# isoSPI_UART_Test_Board_rev1.net
KiCad netlist of a schematic drawn in EAGLE
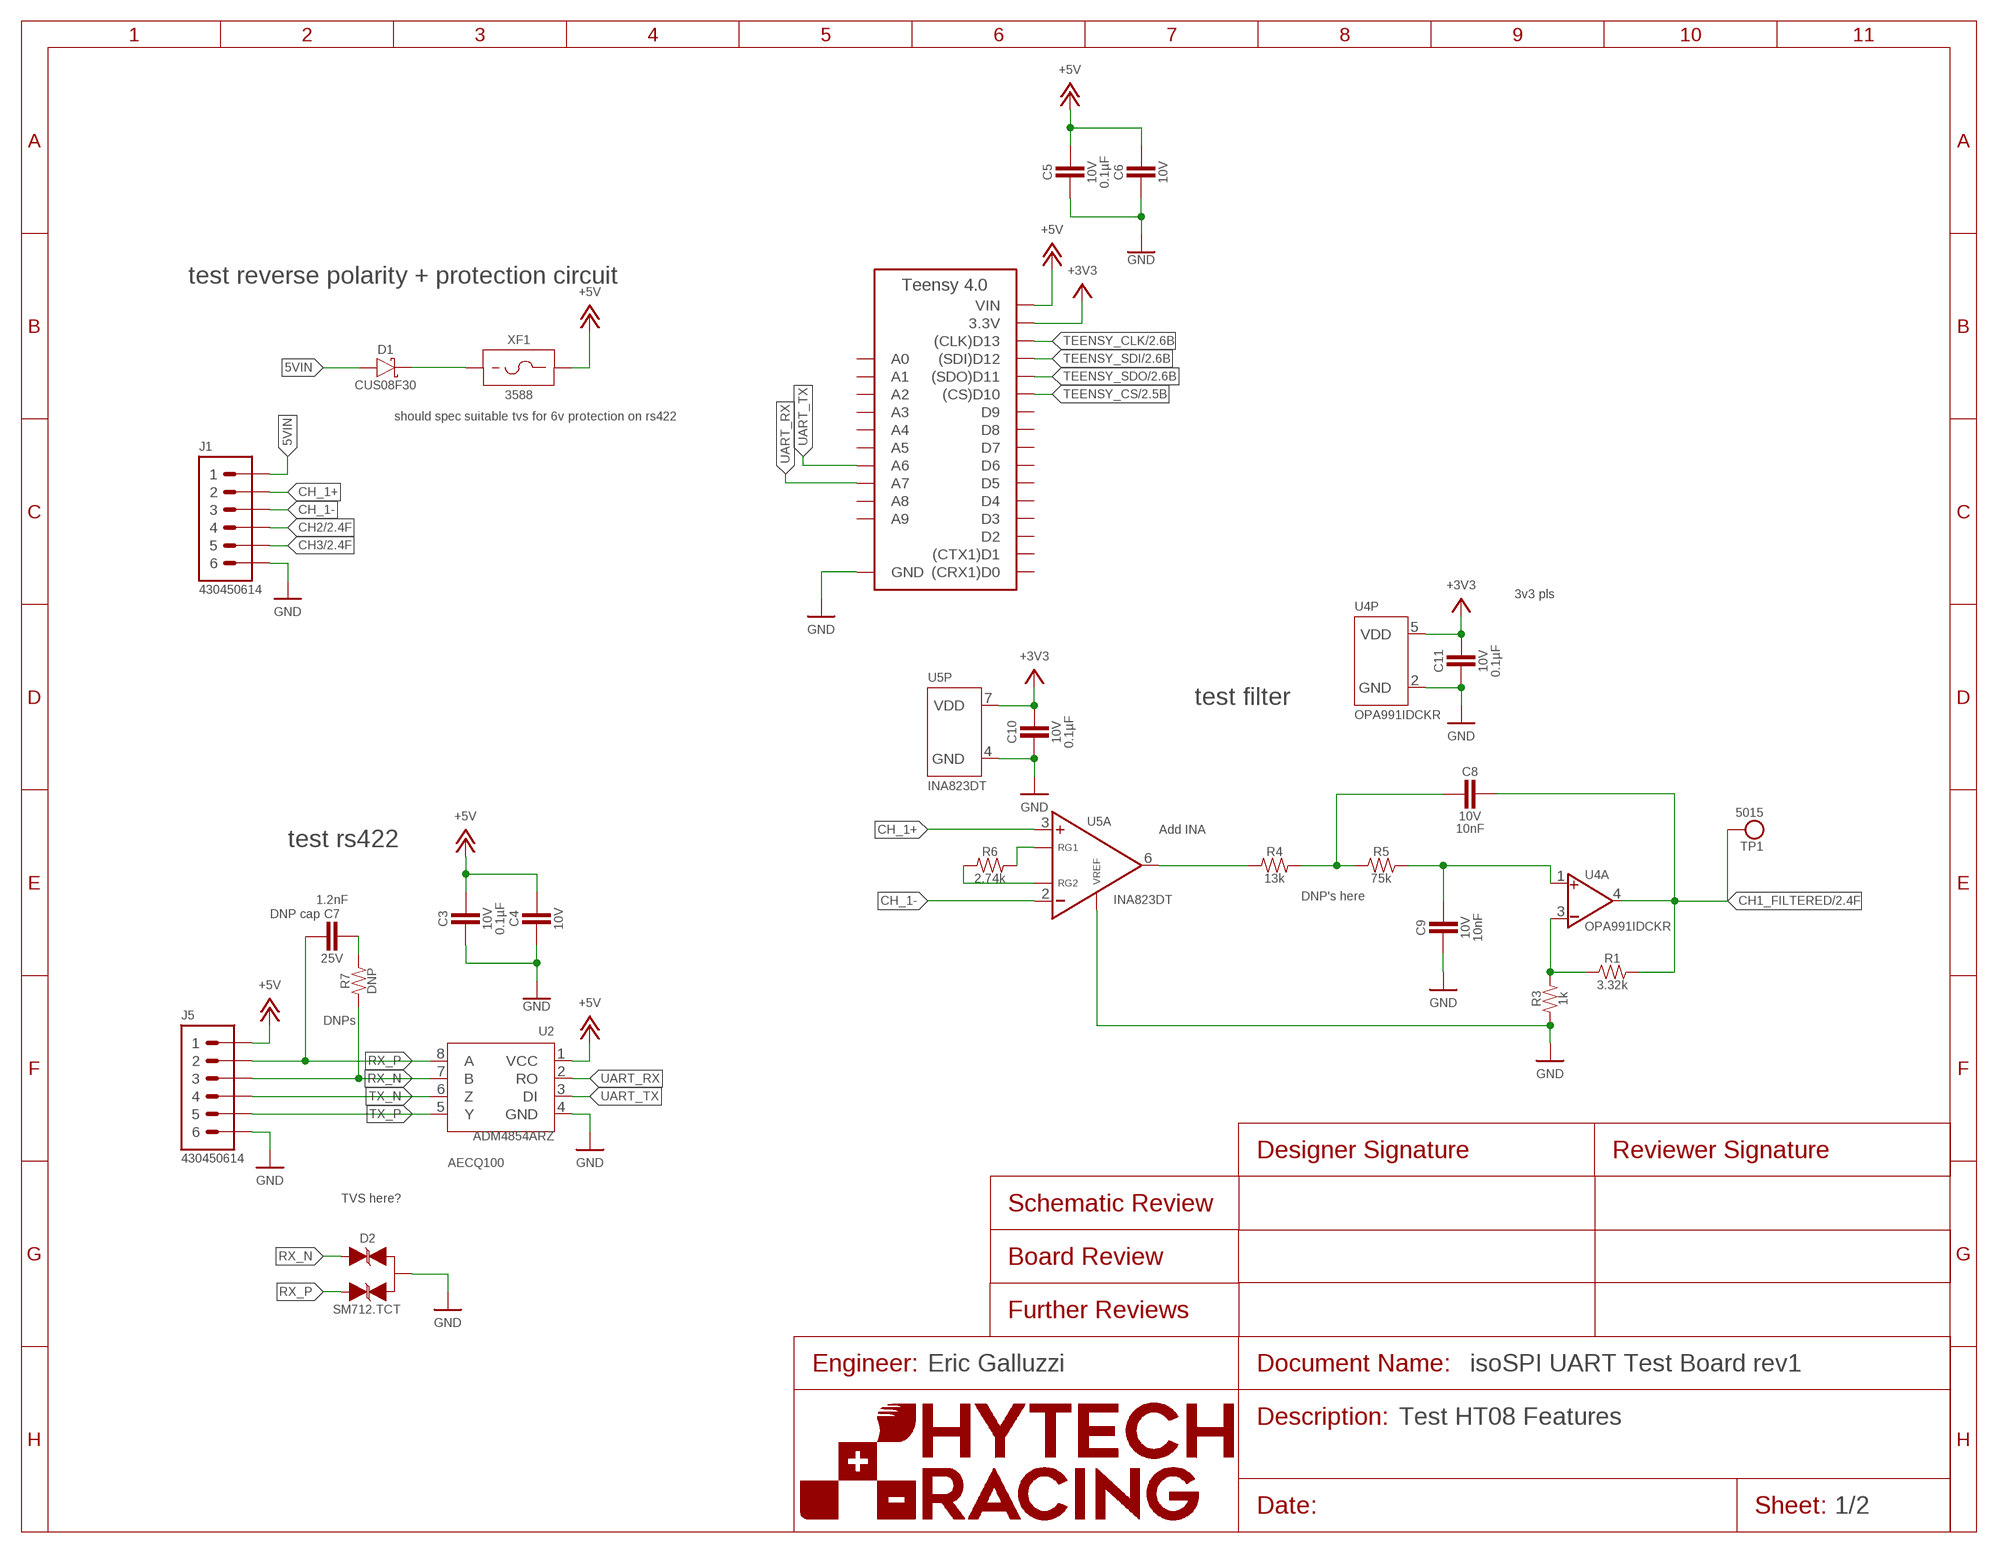
[diagram p0: schematic, sheet 1]
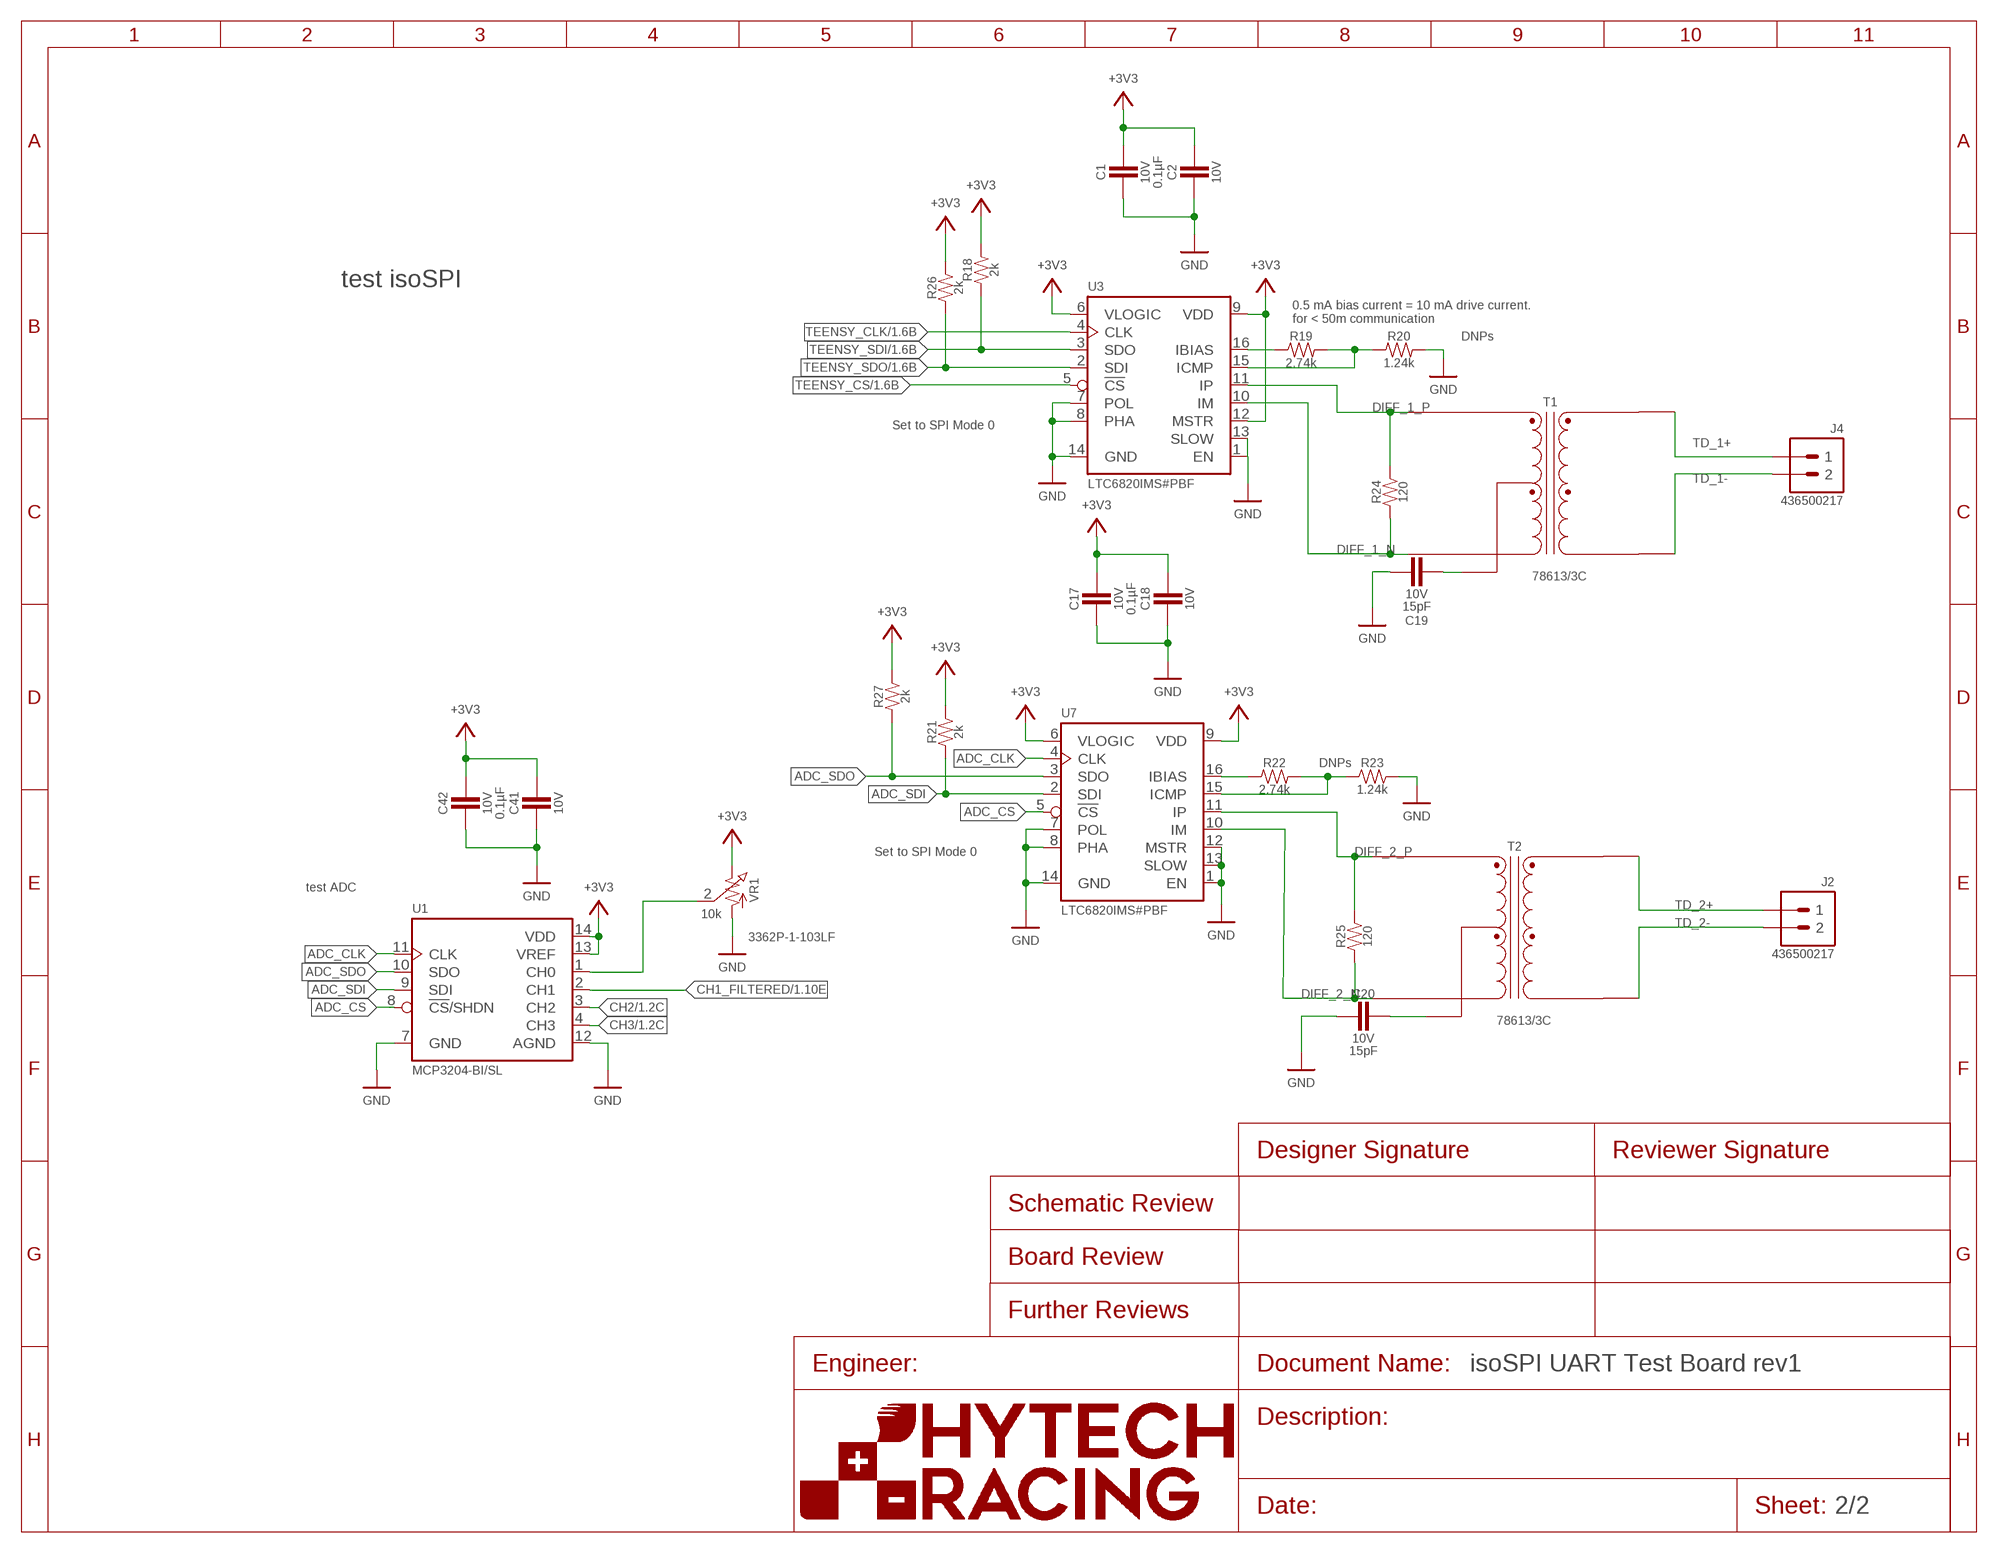
[diagram p1: schematic, sheet 2]

(export (version "E")
  (design (tool "Eeschema 10.0.6"))
  (components
    (comp (ref "C1")
      (value "CAPACITOR_0603_10V_0.1UF")
      (footprint "eagle-import:0603-CAP")
      (fields
        (field (name "CAPACITANCE") "0.1µF")
        (field (name "MANUFACTURER") "Vishay Vitramon")
        (field (name "MPN") "VJ0603Y104JXQPW1BC")
        (field (name "TOLERANCE") "5%")
        (field (name "VOLTAGE") "10V")
      )
      (libsource (lib "eagle-import") (part "CAPACITOR_?_060310V_0.1UF"))
    )
    (comp (ref "C2")
      (value "CAPACITOR_0603_10V_1UF")
      (footprint "eagle-import:0603-CAP")
      (fields
        (field (name "MANUFACTURER") "Yageo")
        (field (name "MPN") "CC0603KRX7R6BB105")
        (field (name "TOLERANCE") "10%")
        (field (name "VOLTAGE") "10V")
      )
      (libsource (lib "eagle-import") (part "CAPACITOR_?_060310V_1UF"))
    )
    (comp (ref "C17")
      (value "CAPACITOR_0603_10V_0.1UF")
      (footprint "eagle-import:0603-CAP")
      (fields
        (field (name "CAPACITANCE") "0.1µF")
        (field (name "MANUFACTURER") "Vishay Vitramon")
        (field (name "MPN") "VJ0603Y104JXQPW1BC")
        (field (name "TOLERANCE") "5%")
        (field (name "VOLTAGE") "10V")
      )
      (libsource (lib "eagle-import") (part "CAPACITOR_?_060310V_0.1UF"))
    )
    (comp (ref "C18")
      (value "CAPACITOR_0603_10V_1UF")
      (footprint "eagle-import:0603-CAP")
      (fields
        (field (name "MANUFACTURER") "Yageo")
        (field (name "MPN") "CC0603KRX7R6BB105")
        (field (name "TOLERANCE") "10%")
        (field (name "VOLTAGE") "10V")
      )
      (libsource (lib "eagle-import") (part "CAPACITOR_?_060310V_1UF"))
    )
    (comp (ref "C19")
      (value "CAPACITOR_0603_10V_15PF")
      (footprint "eagle-import:0603-CAP")
      (fields
        (field (name "CAPACITANCE") "15pF")
        (field (name "MANUFACTURER") "Vishay Vitramon")
        (field (name "MPN") "VJ0603A150FXQPW1BC")
        (field (name "TOLERANCE") "1%")
        (field (name "VOLTAGE") "10V")
      )
      (libsource (lib "eagle-import") (part "CAPACITOR_?_060310V_15PF"))
    )
    (comp (ref "C20")
      (value "CAPACITOR_0603_10V_15PF")
      (footprint "eagle-import:0603-CAP")
      (fields
        (field (name "CAPACITANCE") "15pF")
        (field (name "MANUFACTURER") "Vishay Vitramon")
        (field (name "MPN") "VJ0603A150FXQPW1BC")
        (field (name "TOLERANCE") "1%")
        (field (name "VOLTAGE") "10V")
      )
      (libsource (lib "eagle-import") (part "CAPACITOR_?_060310V_15PF"))
    )
    (comp (ref "C41")
      (value "CAPACITOR_0603_10V_1UF")
      (footprint "eagle-import:0603-CAP")
      (fields
        (field (name "MANUFACTURER") "Yageo")
        (field (name "MPN") "CC0603KRX7R6BB105")
        (field (name "TOLERANCE") "10%")
        (field (name "VOLTAGE") "10V")
      )
      (libsource (lib "eagle-import") (part "CAPACITOR_?_060310V_1UF"))
    )
    (comp (ref "C42")
      (value "CAPACITOR_0603_10V_0.1UF")
      (footprint "eagle-import:0603-CAP")
      (fields
        (field (name "CAPACITANCE") "0.1µF")
        (field (name "MANUFACTURER") "Vishay Vitramon")
        (field (name "MPN") "VJ0603Y104JXQPW1BC")
        (field (name "TOLERANCE") "5%")
        (field (name "VOLTAGE") "10V")
      )
      (libsource (lib "eagle-import") (part "CAPACITOR_?_060310V_0.1UF"))
    )
    (comp (ref "J2")
      (value "CONNECTOR-2_MF_T_V_")
      (footprint "eagle-import:MOLEX_MICROFIT_PTH_VERTICAL_02_SINGLE")
      (fields (field (name "MPN") "436500217") (field (name "MANUFACTURER") "MOLEX"))
      (libsource (lib "eagle-import") (part "CONNECTOR-2_?_MF_T_V"))
    )
    (comp (ref "J4")
      (value "CONNECTOR-2_MF_T_V_")
      (footprint "eagle-import:MOLEX_MICROFIT_PTH_VERTICAL_02_SINGLE")
      (fields (field (name "MPN") "436500217") (field (name "MANUFACTURER") "MOLEX"))
      (libsource (lib "eagle-import") (part "CONNECTOR-2_?_MF_T_V"))
    )
    (comp (ref "R18")
      (value "RESISTOR_0603_2K")
      (footprint "eagle-import:0603-RES")
      (fields
        (field (name "MANUFACTURER") "Panasonic Electronic Components")
        (field (name "MPN") "ERJ-UP3F2001V")
        (field (name "POWER") "0.25W")
        (field (name "RESISTANCE") "2k")
      )
      (libsource (lib "eagle-import") (part "RESISTOR_?_06032K"))
    )
    (comp (ref "R19")
      (value "RESISTOR_0603_2.74K")
      (footprint "eagle-import:0603-RES")
      (fields
        (field (name "MANUFACTURER") "Panasonic Electronic Components")
        (field (name "MPN") "ERJ-PB3B2741V")
        (field (name "POWER") "0.2W")
        (field (name "RESISTANCE") "2.74k")
      )
      (libsource (lib "eagle-import") (part "RESISTOR_?_06032.74K"))
    )
    (comp (ref "R20")
      (value "RESISTOR_0603_1.24K")
      (footprint "eagle-import:0603-RES")
      (fields
        (field (name "MANUFACTURER") "Yageo")
        (field (name "MPN") "RC0603FR-071K24L")
        (field (name "POWER") "0.1W")
        (field (name "RESISTANCE") "1.24k")
      )
      (libsource (lib "eagle-import") (part "RESISTOR_?_06031.24K"))
    )
    (comp (ref "R21")
      (value "RESISTOR_0603_2K")
      (footprint "eagle-import:0603-RES")
      (fields
        (field (name "MANUFACTURER") "Panasonic Electronic Components")
        (field (name "MPN") "ERJ-UP3F2001V")
        (field (name "POWER") "0.25W")
        (field (name "RESISTANCE") "2k")
      )
      (libsource (lib "eagle-import") (part "RESISTOR_?_06032K"))
    )
    (comp (ref "R22")
      (value "RESISTOR_0603_2.74K")
      (footprint "eagle-import:0603-RES")
      (fields
        (field (name "MANUFACTURER") "Panasonic Electronic Components")
        (field (name "MPN") "ERJ-PB3B2741V")
        (field (name "POWER") "0.2W")
        (field (name "RESISTANCE") "2.74k")
      )
      (libsource (lib "eagle-import") (part "RESISTOR_?_06032.74K"))
    )
    (comp (ref "R23")
      (value "RESISTOR_0603_1.24K")
      (footprint "eagle-import:0603-RES")
      (fields
        (field (name "MANUFACTURER") "Yageo")
        (field (name "MPN") "RC0603FR-071K24L")
        (field (name "POWER") "0.1W")
        (field (name "RESISTANCE") "1.24k")
      )
      (libsource (lib "eagle-import") (part "RESISTOR_?_06031.24K"))
    )
    (comp (ref "R24")
      (value "RESISTOR_0603_120")
      (footprint "eagle-import:0603-RES")
      (fields
        (field (name "MANUFACTURER") "Panasonic Electronic Components")
        (field (name "MPN") "ERA-3AEB121V")
        (field (name "POWER") "0.1W")
        (field (name "RESISTANCE") "120")
      )
      (libsource (lib "eagle-import") (part "RESISTOR_?_0603120"))
    )
    (comp (ref "R25")
      (value "RESISTOR_0603_120")
      (footprint "eagle-import:0603-RES")
      (fields
        (field (name "MANUFACTURER") "Panasonic Electronic Components")
        (field (name "MPN") "ERA-3AEB121V")
        (field (name "POWER") "0.1W")
        (field (name "RESISTANCE") "120")
      )
      (libsource (lib "eagle-import") (part "RESISTOR_?_0603120"))
    )
    (comp (ref "R26")
      (value "RESISTOR_0603_2K")
      (footprint "eagle-import:0603-RES")
      (fields
        (field (name "MANUFACTURER") "Panasonic Electronic Components")
        (field (name "MPN") "ERJ-UP3F2001V")
        (field (name "POWER") "0.25W")
        (field (name "RESISTANCE") "2k")
      )
      (libsource (lib "eagle-import") (part "RESISTOR_?_06032K"))
    )
    (comp (ref "R27")
      (value "RESISTOR_0603_2K")
      (footprint "eagle-import:0603-RES")
      (fields
        (field (name "MANUFACTURER") "Panasonic Electronic Components")
        (field (name "MPN") "ERJ-UP3F2001V")
        (field (name "POWER") "0.25W")
        (field (name "RESISTANCE") "2k")
      )
      (libsource (lib "eagle-import") (part "RESISTOR_?_06032K"))
    )
    (comp (ref "T1")
      (value "78613/3C")
      (footprint "eagle-import:78613_3C")
      (fields (field (name "MPN") "78613/3C") (field (name "MANUFACTURER") "Murata Power Solutions"))
      (libsource (lib "eagle-import") (part "78613/3C"))
    )
    (comp (ref "T2")
      (value "78613/3C")
      (footprint "eagle-import:78613_3C")
      (fields (field (name "MPN") "78613/3C") (field (name "MANUFACTURER") "Murata Power Solutions"))
      (libsource (lib "eagle-import") (part "78613/3C"))
    )
    (comp (ref "U1")
      (value "MCP3204")
      (footprint "eagle-import:SOIC-14")
      (fields (field (name "MPN") "MCP3204-BI/SL") (field (name "MANUFACTURER") "Microchip Technology"))
      (libsource (lib "eagle-import") (part "MCP3204"))
    )
    (comp (ref "U3")
      (value "LTC6820")
      (footprint "eagle-import:MSOP-16")
      (fields (field (name "MPN") "LTC6820IMS#PBF") (field (name "MANUFACTURER") "Analog Devices"))
      (libsource (lib "eagle-import") (part "LTC6820"))
    )
    (comp (ref "U7")
      (value "LTC6820")
      (footprint "eagle-import:MSOP-16")
      (fields (field (name "MPN") "LTC6820IMS#PBF") (field (name "MANUFACTURER") "Analog Devices"))
      (libsource (lib "eagle-import") (part "LTC6820"))
    )
    (comp (ref "VR1")
      (value "RESISTOR_TRIMPOT_10K_3362P")
      (footprint "eagle-import:3362P")
      (fields
        (field (name "MANUFACTURER") "Bourns Inc.")
        (field (name "MPN") "3362P-1-103LF")
        (field (name "POWER") "0.5W")
        (field (name "RESISTANCE") "10k")
        (field (name "TOLERANCE") "10%")
      )
      (libsource (lib "eagle-import") (part "RESISTOR_TRIMPOT__?3362P10K"))
    )
    (comp (ref "A1")
      (value "TEENSY_4.0TH")
      (footprint "eagle-import:TEENSY_SHORT")
      (libsource (lib "eagle-import") (part "TEENSY_4.0TH"))
    )
    (comp (ref "C3")
      (value "CAPACITOR_0603_10V_0.1UF")
      (footprint "eagle-import:0603-CAP")
      (fields
        (field (name "CAPACITANCE") "0.1µF")
        (field (name "MANUFACTURER") "Vishay Vitramon")
        (field (name "MPN") "VJ0603Y104JXQPW1BC")
        (field (name "TOLERANCE") "5%")
        (field (name "VOLTAGE") "10V")
      )
      (libsource (lib "eagle-import") (part "CAPACITOR_?_060310V_0.1UF"))
    )
    (comp (ref "C4")
      (value "CAPACITOR_0603_10V_1UF")
      (footprint "eagle-import:0603-CAP")
      (fields
        (field (name "MANUFACTURER") "Yageo")
        (field (name "MPN") "CC0603KRX7R6BB105")
        (field (name "TOLERANCE") "10%")
        (field (name "VOLTAGE") "10V")
      )
      (libsource (lib "eagle-import") (part "CAPACITOR_?_060310V_1UF"))
    )
    (comp (ref "C5")
      (value "CAPACITOR_0603_10V_0.1UF")
      (footprint "eagle-import:0603-CAP")
      (fields
        (field (name "CAPACITANCE") "0.1µF")
        (field (name "MANUFACTURER") "Vishay Vitramon")
        (field (name "MPN") "VJ0603Y104JXQPW1BC")
        (field (name "TOLERANCE") "5%")
        (field (name "VOLTAGE") "10V")
      )
      (libsource (lib "eagle-import") (part "CAPACITOR_?_060310V_0.1UF"))
    )
    (comp (ref "C6")
      (value "CAPACITOR_0603_10V_1UF")
      (footprint "eagle-import:0603-CAP")
      (fields
        (field (name "MANUFACTURER") "Yageo")
        (field (name "MPN") "CC0603KRX7R6BB105")
        (field (name "TOLERANCE") "10%")
        (field (name "VOLTAGE") "10V")
      )
      (libsource (lib "eagle-import") (part "CAPACITOR_?_060310V_1UF"))
    )
    (comp (ref "C7")
      (value "CAPACITOR_0603_25V_1.2NF")
      (footprint "eagle-import:0603-CAP")
      (fields
        (field (name "CAPACITANCE") "1.2nF")
        (field (name "MANUFACTURER") "YAGEO")
        (field (name "MPN") "CC0603KRX7R8BB122")
        (field (name "TOLERANCE") "10%")
        (field (name "VOLTAGE") "25V")
      )
      (libsource (lib "eagle-import") (part "CAPACITOR_?_060325V_1.2NF"))
    )
    (comp (ref "C8")
      (value "CAPACITOR_0603_10V_10NF")
      (footprint "eagle-import:0603-CAP")
      (fields
        (field (name "CAPACITANCE") "10nF")
        (field (name "MANUFACTURER") "Yageo")
        (field (name "MPN") "CC0603KRX7R6BB103")
        (field (name "TOLERANCE") "10%")
        (field (name "VOLTAGE") "10V")
      )
      (libsource (lib "eagle-import") (part "CAPACITOR_?_060310V_10NF"))
    )
    (comp (ref "C9")
      (value "CAPACITOR_0603_10V_10NF")
      (footprint "eagle-import:0603-CAP")
      (fields
        (field (name "CAPACITANCE") "10nF")
        (field (name "MANUFACTURER") "Yageo")
        (field (name "MPN") "CC0603KRX7R6BB103")
        (field (name "TOLERANCE") "10%")
        (field (name "VOLTAGE") "10V")
      )
      (libsource (lib "eagle-import") (part "CAPACITOR_?_060310V_10NF"))
    )
    (comp (ref "C10")
      (value "CAPACITOR_0603_10V_0.1UF")
      (footprint "eagle-import:0603-CAP")
      (fields
        (field (name "CAPACITANCE") "0.1µF")
        (field (name "MANUFACTURER") "Vishay Vitramon")
        (field (name "MPN") "VJ0603Y104JXQPW1BC")
        (field (name "TOLERANCE") "5%")
        (field (name "VOLTAGE") "10V")
      )
      (libsource (lib "eagle-import") (part "CAPACITOR_?_060310V_0.1UF"))
    )
    (comp (ref "C11")
      (value "CAPACITOR_0603_10V_0.1UF")
      (footprint "eagle-import:0603-CAP")
      (fields
        (field (name "CAPACITANCE") "0.1µF")
        (field (name "MANUFACTURER") "Vishay Vitramon")
        (field (name "MPN") "VJ0603Y104JXQPW1BC")
        (field (name "TOLERANCE") "5%")
        (field (name "VOLTAGE") "10V")
      )
      (libsource (lib "eagle-import") (part "CAPACITOR_?_060310V_0.1UF"))
    )
    (comp (ref "D1")
      (value "SCHOTTKY_SOD323_30V")
      (footprint "eagle-import:SOD-323")
      (fields
        (field (name "MANUFACTURER") "Toshiba Semiconductor and Storage")
        (field (name "MPN") "CUS08F30")
        (field (name "VOLTAGE") "30V")
      )
      (libsource (lib "eagle-import") (part "SCHOTTKY_?_SOD32330V"))
    )
    (comp (ref "D2")
      (value "TVS_BIDIRECTIONAL_DUALRS422")
      (footprint "eagle-import:SOT-23")
      (fields (field (name "MPN") "SM712.TCT") (field (name "MANUFACTURER") "Semtech Corporation"))
      (libsource (lib "eagle-import") (part "TVS_BIDIRECTIONAL_DUALRS422"))
    )
    (comp (ref "J1")
      (value "CONNECTOR-6_μF_T_V_BLACK")
      (footprint "eagle-import:MOLEX_MICROFIT_PTH_VERTICAL_06_DUAL")
      (fields (field (name "MANUFACTURER") "Molex") (field (name "MPN") "430450614"))
      (libsource (lib "eagle-import") (part "CONNECTOR-6_?_μF_T_VBLACK"))
    )
    (comp (ref "J5")
      (value "CONNECTOR-6_μF_T_V_BLACK")
      (footprint "eagle-import:MOLEX_MICROFIT_PTH_VERTICAL_06_DUAL")
      (fields (field (name "MANUFACTURER") "Molex") (field (name "MPN") "430450614"))
      (libsource (lib "eagle-import") (part "CONNECTOR-6_?_μF_T_VBLACK"))
    )
    (comp (ref "R1")
      (value "RESISTOR_0603_3.32K")
      (footprint "eagle-import:0603-RES")
      (fields
        (field (name "MANUFACTURER") "Yageo")
        (field (name "MPN") "RT0603BRD073K32L")
        (field (name "POWER") "0.1W")
        (field (name "RESISTANCE") "3.32k")
      )
      (libsource (lib "eagle-import") (part "RESISTOR_?_06033.32K"))
    )
    (comp (ref "R3")
      (value "RESISTOR_0603_1K")
      (footprint "eagle-import:0603-RES")
      (fields
        (field (name "MANUFACTURER") "TE Connectivity Passive Product")
        (field (name "MPN") " CPF-A-0603B1K0E")
        (field (name "POWER") "0.0625W")
        (field (name "RESISTANCE") "1k")
      )
      (libsource (lib "eagle-import") (part "RESISTOR_?_06031K"))
    )
    (comp (ref "R4")
      (value "RESISTOR_0603_13K")
      (footprint "eagle-import:0603-RES")
      (fields
        (field (name "MANUFACTURER") "Panasonic Electronic Components")
        (field (name "MPN") "ERA-3ARW133V")
        (field (name "POWER") "0.1W")
        (field (name "RESISTANCE") "13k")
      )
      (libsource (lib "eagle-import") (part "RESISTOR_?_060313K"))
    )
    (comp (ref "R5")
      (value "RESISTOR_0603_75K")
      (footprint "eagle-import:0603-RES")
      (fields
        (field (name "MANUFACTURER") "Yageo")
        (field (name "MPN") "RT0603BRE0775KL")
        (field (name "POWER") "0.1W")
        (field (name "RESISTANCE") "75k")
      )
      (libsource (lib "eagle-import") (part "RESISTOR_?_060375K"))
    )
    (comp (ref "R6")
      (value "RESISTOR_0603_2.74K")
      (footprint "eagle-import:0603-RES")
      (fields
        (field (name "MANUFACTURER") "Panasonic Electronic Components")
        (field (name "MPN") "ERJ-PB3B2741V")
        (field (name "POWER") "0.2W")
        (field (name "RESISTANCE") "2.74k")
      )
      (libsource (lib "eagle-import") (part "RESISTOR_?_06032.74K"))
    )
    (comp (ref "R7")
      (value "RESISTOR_0603_DNP")
      (footprint "eagle-import:0603-RES")
      (fields (field (name "RESISTANCE") "DNP"))
      (libsource (lib "eagle-import") (part "RESISTOR_?_0603DNP"))
    )
    (comp (ref "TP1")
      (value "TEST_POINT")
      (footprint "eagle-import:5015")
      (fields (field (name "MPN") "5015") (field (name "MANUFACTURER") "Keystone Electronics"))
      (libsource (lib "eagle-import") (part "TEST_POINT"))
    )
    (comp (ref "U2")
      (value "ADM4854ARZ")
      (footprint "eagle-import:SOIC-08(NARROW,0.15_)")
      (fields (field (name "MPN") "ADM4854ARZ") (field (name "MANUFACTURER") "Analog Devices Inc."))
      (libsource (lib "eagle-import") (part "ADM4854ARZ"))
    )
    (comp (ref "U4")
      (value "OPAMP_1_CHANNEL_OPA991")
      (footprint "eagle-import:SC-70-5")
      (fields (field (name "MANUFACTURER") "Texas Instruments") (field (name "MPN") "OPA991IDCKR"))
      (libsource (lib "eagle-import") (part "OPAMP_1_CHANNEL_OPA991"))
    )
    (comp (ref "U5")
      (value "INA823DT")
      (footprint "eagle-import:SOIC-08(NARROW,0.15_)")
      (fields (field (name "MANUFACTURER") "Texas Instruments") (field (name "MPN") "INA823DT"))
      (libsource (lib "eagle-import") (part "INA823DT"))
    )
    (comp (ref "XF1")
      (value "FUSE_HOLDER_MINIBLADESMD")
      (footprint "eagle-import:3588")
      (fields (field (name "MANUFACTURER") "Keystone Electronics") (field (name "MPN") "3588"))
      (libsource (lib "eagle-import") (part "FUSE_HOLDER_SMDMINIBLADE"))
    )
  )
  (nets
    (net (code "1") (name "+5V") (class "Default")
      (node (ref "A1") (pin "VIN") (pinfunction "VIN_VIN") (pintype "power_in"))
      (node (ref "C3") (pin "1") (pinfunction "1_1") (pintype "passive"))
      (node (ref "C4") (pin "1") (pinfunction "1_1") (pintype "passive"))
      (node (ref "C5") (pin "1") (pinfunction "1_1") (pintype "passive"))
      (node (ref "C6") (pin "1") (pinfunction "1_1") (pintype "passive"))
      (node (ref "J5") (pin "1") (pinfunction "1_1") (pintype "passive"))
      (node (ref "U2") (pin "1") (pinfunction "VCC_1") (pintype "passive"))
      (node (ref "XF1") (pin "3") (pinfunction "2_3") (pintype "passive"))
      (node (ref "XF1") (pin "4") (pinfunction "2_4") (pintype "passive"))
    )
    (net (code "2") (name "5VIN") (class "Default")
      (node (ref "D1") (pin "A") (pinfunction "A_A") (pintype "passive"))
      (node (ref "J1") (pin "1") (pinfunction "1_1") (pintype "passive"))
    )
    (net (code "3") (name "ADC_CLK") (class "Default")
      (node (ref "U1") (pin "11") (pinfunction "CLK_11") (pintype "input"))
      (node (ref "U7") (pin "4") (pinfunction "CLK_4") (pintype "input"))
    )
    (net (code "4") (name "ADC_CS") (class "Default")
      (node (ref "U1") (pin "8") (pinfunction "~{CS}/SHDN_8") (pintype "input"))
      (node (ref "U7") (pin "5") (pinfunction "~{CS}_5") (pintype "input"))
    )
    (net (code "5") (name "ADC_SDI") (class "Default")
      (node (ref "R21") (pin "1") (pinfunction "1_1") (pintype "passive"))
      (node (ref "U1") (pin "9") (pinfunction "SDI_9") (pintype "input"))
      (node (ref "U7") (pin "2") (pinfunction "SDI_2") (pintype "open_collector"))
    )
    (net (code "6") (name "ADC_SDO") (class "Default")
      (node (ref "R27") (pin "1") (pinfunction "1_1") (pintype "passive"))
      (node (ref "U1") (pin "10") (pinfunction "SDO_10") (pintype "output"))
      (node (ref "U7") (pin "3") (pinfunction "SDO_3") (pintype "open_collector"))
    )
    (net (code "7") (name "CH1_FILTERED") (class "Default")
      (node (ref "C8") (pin "1") (pinfunction "1_1") (pintype "passive"))
      (node (ref "R1") (pin "2") (pinfunction "2_2") (pintype "passive"))
      (node (ref "TP1") (pin "1") (pinfunction "1_1") (pintype "passive"))
      (node (ref "U1") (pin "2") (pinfunction "CH1_2") (pintype "input"))
      (node (ref "U4") (pin "4") (pinfunction "VOUT_4") (pintype "output"))
    )
    (net (code "8") (name "CH2") (class "Default")
      (node (ref "J1") (pin "4") (pinfunction "4_4") (pintype "passive"))
      (node (ref "U1") (pin "3") (pinfunction "CH2_3") (pintype "input"))
    )
    (net (code "9") (name "CH3") (class "Default")
      (node (ref "J1") (pin "5") (pinfunction "5_5") (pintype "passive"))
      (node (ref "U1") (pin "4") (pinfunction "CH3_4") (pintype "input"))
    )
    (net (code "10") (name "CH_1+") (class "Default")
      (node (ref "J1") (pin "2") (pinfunction "2_2") (pintype "passive"))
      (node (ref "U5") (pin "3") (pinfunction "VIN+_3") (pintype "input"))
    )
    (net (code "11") (name "CH_1-") (class "Default")
      (node (ref "J1") (pin "3") (pinfunction "3_3") (pintype "passive"))
      (node (ref "U5") (pin "2") (pinfunction "VIN-_2") (pintype "input"))
    )
    (net (code "12") (name "DIFF_1_N") (class "Default")
      (node (ref "R24") (pin "1") (pinfunction "1_1") (pintype "passive"))
      (node (ref "T1") (pin "3") (pinfunction "PRI_2_3") (pintype "passive"))
      (node (ref "U3") (pin "10") (pinfunction "IM_10") (pintype "bidirectional"))
    )
    (net (code "13") (name "DIFF_1_P") (class "Default")
      (node (ref "R24") (pin "2") (pinfunction "2_2") (pintype "passive"))
      (node (ref "T1") (pin "1") (pinfunction "PRI_1_1") (pintype "passive"))
      (node (ref "U3") (pin "11") (pinfunction "IP_11") (pintype "bidirectional"))
    )
    (net (code "14") (name "DIFF_2_N") (class "Default")
      (node (ref "R25") (pin "1") (pinfunction "1_1") (pintype "passive"))
      (node (ref "T2") (pin "3") (pinfunction "PRI_2_3") (pintype "passive"))
      (node (ref "U7") (pin "10") (pinfunction "IM_10") (pintype "bidirectional"))
    )
    (net (code "15") (name "DIFF_2_P") (class "Default")
      (node (ref "R25") (pin "2") (pinfunction "2_2") (pintype "passive"))
      (node (ref "T2") (pin "1") (pinfunction "PRI_1_1") (pintype "passive"))
      (node (ref "U7") (pin "11") (pinfunction "IP_11") (pintype "bidirectional"))
    )
    (net (code "16") (name "GND") (class "Default")
      (node (ref "A1") (pin "AGND/GND") (pinfunction "GND_AGND/GND") (pintype "power_in"))
      (node (ref "A1") (pin "GND") (pinfunction "GND_GND") (pintype "power_in"))
      (node (ref "C1") (pin "2") (pinfunction "2_2") (pintype "passive"))
      (node (ref "C10") (pin "2") (pinfunction "2_2") (pintype "passive"))
      (node (ref "C11") (pin "2") (pinfunction "2_2") (pintype "passive"))
      (node (ref "C17") (pin "2") (pinfunction "2_2") (pintype "passive"))
      (node (ref "C18") (pin "2") (pinfunction "2_2") (pintype "passive"))
      (node (ref "C19") (pin "2") (pinfunction "2_2") (pintype "passive"))
      (node (ref "C2") (pin "2") (pinfunction "2_2") (pintype "passive"))
      (node (ref "C20") (pin "2") (pinfunction "2_2") (pintype "passive"))
      (node (ref "C3") (pin "2") (pinfunction "2_2") (pintype "passive"))
      (node (ref "C4") (pin "2") (pinfunction "2_2") (pintype "passive"))
      (node (ref "C41") (pin "2") (pinfunction "2_2") (pintype "passive"))
      (node (ref "C42") (pin "2") (pinfunction "2_2") (pintype "passive"))
      (node (ref "C5") (pin "2") (pinfunction "2_2") (pintype "passive"))
      (node (ref "C6") (pin "2") (pinfunction "2_2") (pintype "passive"))
      (node (ref "C9") (pin "2") (pinfunction "2_2") (pintype "passive"))
      (node (ref "D2") (pin "3") (pinfunction "A_3") (pintype "passive"))
      (node (ref "J1") (pin "6") (pinfunction "6_6") (pintype "passive"))
      (node (ref "J5") (pin "6") (pinfunction "6_6") (pintype "passive"))
      (node (ref "R20") (pin "2") (pinfunction "2_2") (pintype "passive"))
      (node (ref "R23") (pin "2") (pinfunction "2_2") (pintype "passive"))
      (node (ref "R3") (pin "1") (pinfunction "1_1") (pintype "passive"))
      (node (ref "U1") (pin "12") (pinfunction "AGND_12") (pintype "power_in"))
      (node (ref "U1") (pin "7") (pinfunction "GND_7") (pintype "power_in"))
      (node (ref "U2") (pin "4") (pinfunction "GND_4") (pintype "passive"))
      (node (ref "U3") (pin "1") (pinfunction "EN_1") (pintype "passive"))
      (node (ref "U3") (pin "13") (pinfunction "SLOW_13") (pintype "passive"))
      (node (ref "U3") (pin "14") (pinfunction "GND_14") (pintype "power_in"))
      (node (ref "U3") (pin "7") (pinfunction "POL_7") (pintype "passive"))
      (node (ref "U3") (pin "8") (pinfunction "PHA_8") (pintype "passive"))
      (node (ref "U4") (pin "2") (pinfunction "GND_2") (pintype "power_in"))
      (node (ref "U5") (pin "4") (pinfunction "GND_4") (pintype "power_in"))
      (node (ref "U5") (pin "5") (pinfunction "VREF_5") (pintype "input"))
      (node (ref "U7") (pin "1") (pinfunction "EN_1") (pintype "passive"))
      (node (ref "U7") (pin "12") (pinfunction "MSTR_12") (pintype "passive"))
      (node (ref "U7") (pin "13") (pinfunction "SLOW_13") (pintype "passive"))
      (node (ref "U7") (pin "14") (pinfunction "GND_14") (pintype "power_in"))
      (node (ref "U7") (pin "7") (pinfunction "POL_7") (pintype "passive"))
      (node (ref "U7") (pin "8") (pinfunction "PHA_8") (pintype "passive"))
      (node (ref "VR1") (pin "1") (pinfunction "1_1") (pintype "passive"))
    )
    (net (code "17") (name "Net-(C7-Pad1)") (class "Default")
      (node (ref "C7") (pin "1") (pinfunction "1_1") (pintype "passive"))
      (node (ref "R7") (pin "2") (pinfunction "2_2") (pintype "passive"))
    )
    (net (code "18") (name "Net-(C8-Pad2)") (class "Default")
      (node (ref "C8") (pin "2") (pinfunction "2_2") (pintype "passive"))
      (node (ref "R4") (pin "2") (pinfunction "2_2") (pintype "passive"))
      (node (ref "R5") (pin "1") (pinfunction "1_1") (pintype "passive"))
    )
    (net (code "19") (name "Net-(D1-PadC)") (class "Default")
      (node (ref "D1") (pin "C") (pinfunction "C_C") (pintype "passive"))
      (node (ref "XF1") (pin "1") (pinfunction "1_1") (pintype "passive"))
      (node (ref "XF1") (pin "2") (pinfunction "1_2") (pintype "passive"))
    )
    (net (code "20") (name "Net-(T1-PRI_CENTER_TAP)") (class "Default")
      (node (ref "C19") (pin "1") (pinfunction "1_1") (pintype "passive"))
      (node (ref "T1") (pin "2") (pinfunction "PRI_CENTER_TAP_2") (pintype "passive"))
    )
    (net (code "21") (name "Net-(T2-PRI_CENTER_TAP)") (class "Default")
      (node (ref "C20") (pin "1") (pinfunction "1_1") (pintype "passive"))
      (node (ref "T2") (pin "2") (pinfunction "PRI_CENTER_TAP_2") (pintype "passive"))
    )
    (net (code "22") (name "Net-(U1-CH0)") (class "Default")
      (node (ref "U1") (pin "1") (pinfunction "CH0_1") (pintype "input"))
      (node (ref "VR1") (pin "2") (pinfunction "3_2") (pintype "passive"))
    )
    (net (code "23") (name "Net-(U3-IBIAS)") (class "Default")
      (node (ref "R19") (pin "1") (pinfunction "1_1") (pintype "passive"))
      (node (ref "U3") (pin "16") (pinfunction "IBIAS_16") (pintype "bidirectional"))
    )
    (net (code "24") (name "Net-(U3-ICMP)") (class "Default")
      (node (ref "R19") (pin "2") (pinfunction "2_2") (pintype "passive"))
      (node (ref "R20") (pin "1") (pinfunction "1_1") (pintype "passive"))
      (node (ref "U3") (pin "15") (pinfunction "ICMP_15") (pintype "bidirectional"))
    )
    (net (code "25") (name "Net-(U4A-VIN+)") (class "Default")
      (node (ref "C9") (pin "1") (pinfunction "1_1") (pintype "passive"))
      (node (ref "R5") (pin "2") (pinfunction "2_2") (pintype "passive"))
      (node (ref "U4") (pin "1") (pinfunction "VIN+_1") (pintype "input"))
    )
    (net (code "26") (name "Net-(U4A-VIN-)") (class "Default")
      (node (ref "R1") (pin "1") (pinfunction "1_1") (pintype "passive"))
      (node (ref "R3") (pin "2") (pinfunction "2_2") (pintype "passive"))
      (node (ref "U4") (pin "3") (pinfunction "VIN-_3") (pintype "input"))
    )
    (net (code "27") (name "Net-(U5A-RG1)") (class "Default")
      (node (ref "R6") (pin "2") (pinfunction "2_2") (pintype "passive"))
      (node (ref "U5") (pin "1") (pinfunction "RG1_1") (pintype "bidirectional"))
    )
    (net (code "28") (name "Net-(U5A-RG2)") (class "Default")
      (node (ref "R6") (pin "1") (pinfunction "1_1") (pintype "passive"))
      (node (ref "U5") (pin "8") (pinfunction "RG2_8") (pintype "bidirectional"))
    )
    (net (code "29") (name "Net-(U5A-VOUT)") (class "Default")
      (node (ref "R4") (pin "1") (pinfunction "1_1") (pintype "passive"))
      (node (ref "U5") (pin "6") (pinfunction "VOUT_6") (pintype "output"))
    )
    (net (code "30") (name "Net-(U7-IBIAS)") (class "Default")
      (node (ref "R22") (pin "1") (pinfunction "1_1") (pintype "passive"))
      (node (ref "U7") (pin "16") (pinfunction "IBIAS_16") (pintype "bidirectional"))
    )
    (net (code "31") (name "Net-(U7-ICMP)") (class "Default")
      (node (ref "R22") (pin "2") (pinfunction "2_2") (pintype "passive"))
      (node (ref "R23") (pin "1") (pinfunction "1_1") (pintype "passive"))
      (node (ref "U7") (pin "15") (pinfunction "ICMP_15") (pintype "bidirectional"))
    )
    (net (code "32") (name "RX_N") (class "Default")
      (node (ref "D2") (pin "1") (pinfunction "C1_1") (pintype "passive"))
      (node (ref "J5") (pin "3") (pinfunction "3_3") (pintype "passive"))
      (node (ref "R7") (pin "1") (pinfunction "1_1") (pintype "passive"))
      (node (ref "U2") (pin "7") (pinfunction "B_7") (pintype "passive"))
    )
    (net (code "33") (name "RX_P") (class "Default")
      (node (ref "C7") (pin "2") (pinfunction "2_2") (pintype "passive"))
      (node (ref "D2") (pin "2") (pinfunction "C2_2") (pintype "passive"))
      (node (ref "J5") (pin "2") (pinfunction "2_2") (pintype "passive"))
      (node (ref "U2") (pin "8") (pinfunction "A_8") (pintype "passive"))
    )
    (net (code "34") (name "TD_1+") (class "Default")
      (node (ref "J4") (pin "1") (pinfunction "1_1") (pintype "passive"))
      (node (ref "T1") (pin "6") (pinfunction "SEC_2_6") (pintype "passive"))
    )
    (net (code "35") (name "TD_1-") (class "Default")
      (node (ref "J4") (pin "2") (pinfunction "2_2") (pintype "passive"))
      (node (ref "T1") (pin "4") (pinfunction "SEC_1_4") (pintype "passive"))
    )
    (net (code "36") (name "TD_2+") (class "Default")
      (node (ref "J2") (pin "1") (pinfunction "1_1") (pintype "passive"))
      (node (ref "T2") (pin "6") (pinfunction "SEC_2_6") (pintype "passive"))
    )
    (net (code "37") (name "TD_2-") (class "Default")
      (node (ref "J2") (pin "2") (pinfunction "2_2") (pintype "passive"))
      (node (ref "T2") (pin "4") (pinfunction "SEC_1_4") (pintype "passive"))
    )
    (net (code "38") (name "TEENSY_CLK") (class "Default")
      (node (ref "A1") (pin "D13") (pinfunction "(CLK)D13_D13") (pintype "bidirectional"))
      (node (ref "U3") (pin "4") (pinfunction "CLK_4") (pintype "input"))
    )
    (net (code "39") (name "TEENSY_CS") (class "Default")
      (node (ref "A1") (pin "D10") (pinfunction "(CS)D10_D10") (pintype "bidirectional"))
      (node (ref "U3") (pin "5") (pinfunction "~{CS}_5") (pintype "input"))
    )
    (net (code "40") (name "TEENSY_SDI") (class "Default")
      (node (ref "A1") (pin "D12") (pinfunction "(SDI)D12_D12") (pintype "bidirectional"))
      (node (ref "R18") (pin "1") (pinfunction "1_1") (pintype "passive"))
      (node (ref "U3") (pin "3") (pinfunction "SDO_3") (pintype "open_collector"))
    )
    (net (code "41") (name "TEENSY_SDO") (class "Default")
      (node (ref "A1") (pin "D11") (pinfunction "(SDO)D11_D11") (pintype "bidirectional"))
      (node (ref "R26") (pin "1") (pinfunction "1_1") (pintype "passive"))
      (node (ref "U3") (pin "2") (pinfunction "SDI_2") (pintype "open_collector"))
    )
    (net (code "42") (name "TX_N") (class "Default")
      (node (ref "J5") (pin "4") (pinfunction "4_4") (pintype "passive"))
      (node (ref "U2") (pin "6") (pinfunction "Z_6") (pintype "passive"))
    )
    (net (code "43") (name "TX_P") (class "Default")
      (node (ref "J5") (pin "5") (pinfunction "5_5") (pintype "passive"))
      (node (ref "U2") (pin "5") (pinfunction "Y_5") (pintype "passive"))
    )
    (net (code "44") (name "UART_RX") (class "Default")
      (node (ref "A1") (pin "D21") (pinfunction "A7_D21") (pintype "bidirectional"))
      (node (ref "U2") (pin "2") (pinfunction "RO_2") (pintype "passive"))
    )
    (net (code "45") (name "UART_TX") (class "Default")
      (node (ref "A1") (pin "D20") (pinfunction "A6_D20") (pintype "bidirectional"))
      (node (ref "U2") (pin "3") (pinfunction "DI_3") (pintype "passive"))
    )
    (net (code "46") (name "VDD") (class "Default")
      (node (ref "A1") (pin "3.3V") (pinfunction "3.3V_3.3V") (pintype "power_in"))
      (node (ref "C1") (pin "1") (pinfunction "1_1") (pintype "passive"))
      (node (ref "C10") (pin "1") (pinfunction "1_1") (pintype "passive"))
      (node (ref "C11") (pin "1") (pinfunction "1_1") (pintype "passive"))
      (node (ref "C17") (pin "1") (pinfunction "1_1") (pintype "passive"))
      (node (ref "C18") (pin "1") (pinfunction "1_1") (pintype "passive"))
      (node (ref "C2") (pin "1") (pinfunction "1_1") (pintype "passive"))
      (node (ref "C41") (pin "1") (pinfunction "1_1") (pintype "passive"))
      (node (ref "C42") (pin "1") (pinfunction "1_1") (pintype "passive"))
      (node (ref "R18") (pin "2") (pinfunction "2_2") (pintype "passive"))
      (node (ref "R21") (pin "2") (pinfunction "2_2") (pintype "passive"))
      (node (ref "R26") (pin "2") (pinfunction "2_2") (pintype "passive"))
      (node (ref "R27") (pin "2") (pinfunction "2_2") (pintype "passive"))
      (node (ref "U1") (pin "13") (pinfunction "VREF_13") (pintype "power_in"))
      (node (ref "U1") (pin "14") (pinfunction "VDD_14") (pintype "power_in"))
      (node (ref "U3") (pin "12") (pinfunction "MSTR_12") (pintype "passive"))
      (node (ref "U3") (pin "6") (pinfunction "VLOGIC_6") (pintype "bidirectional"))
      (node (ref "U3") (pin "9") (pinfunction "VDD_9") (pintype "power_in"))
      (node (ref "U4") (pin "5") (pinfunction "VDD_5") (pintype "power_in"))
      (node (ref "U5") (pin "7") (pinfunction "VDD_7") (pintype "power_in"))
      (node (ref "U7") (pin "6") (pinfunction "VLOGIC_6") (pintype "bidirectional"))
      (node (ref "U7") (pin "9") (pinfunction "VDD_9") (pintype "power_in"))
      (node (ref "VR1") (pin "3") (pinfunction "2_3") (pintype "passive"))
    )
    (net (code "47") (name "unconnected-(A1-(CRX1)D0-PadD0)") (class "Default")
      (node (ref "A1") (pin "D0") (pinfunction "(CRX1)D0_D0") (pintype "bidirectional"))
    )
    (net (code "48") (name "unconnected-(A1-(CTX1)D1-PadD1)") (class "Default")
      (node (ref "A1") (pin "D1") (pinfunction "(CTX1)D1_D1") (pintype "bidirectional"))
    )
    (net (code "49") (name "unconnected-(A1-A0-PadD14)") (class "Default")
      (node (ref "A1") (pin "D14") (pinfunction "A0_D14") (pintype "bidirectional"))
    )
    (net (code "50") (name "unconnected-(A1-A1-PadD15)") (class "Default")
      (node (ref "A1") (pin "D15") (pinfunction "A1_D15") (pintype "bidirectional"))
    )
    (net (code "51") (name "unconnected-(A1-A2-PadD16)") (class "Default")
      (node (ref "A1") (pin "D16") (pinfunction "A2_D16") (pintype "bidirectional"))
    )
    (net (code "52") (name "unconnected-(A1-A3-PadD17)") (class "Default")
      (node (ref "A1") (pin "D17") (pinfunction "A3_D17") (pintype "bidirectional"))
    )
    (net (code "53") (name "unconnected-(A1-A4-PadD18)") (class "Default")
      (node (ref "A1") (pin "D18") (pinfunction "A4_D18") (pintype "bidirectional"))
    )
    (net (code "54") (name "unconnected-(A1-A5-PadD19)") (class "Default")
      (node (ref "A1") (pin "D19") (pinfunction "A5_D19") (pintype "bidirectional"))
    )
    (net (code "55") (name "unconnected-(A1-A8-PadD22)") (class "Default")
      (node (ref "A1") (pin "D22") (pinfunction "A8_D22") (pintype "bidirectional"))
    )
    (net (code "56") (name "unconnected-(A1-A9-PadD23)") (class "Default")
      (node (ref "A1") (pin "D23") (pinfunction "A9_D23") (pintype "bidirectional"))
    )
    (net (code "57") (name "unconnected-(A1-PadD2)") (class "Default")
      (node (ref "A1") (pin "D2") (pinfunction "D2_D2") (pintype "bidirectional"))
    )
    (net (code "58") (name "unconnected-(A1-PadD3)") (class "Default")
      (node (ref "A1") (pin "D3") (pinfunction "D3_D3") (pintype "bidirectional"))
    )
    (net (code "59") (name "unconnected-(A1-PadD4)") (class "Default")
      (node (ref "A1") (pin "D4") (pinfunction "D4_D4") (pintype "bidirectional"))
    )
    (net (code "60") (name "unconnected-(A1-PadD5)") (class "Default")
      (node (ref "A1") (pin "D5") (pinfunction "D5_D5") (pintype "bidirectional"))
    )
    (net (code "61") (name "unconnected-(A1-PadD6)") (class "Default")
      (node (ref "A1") (pin "D6") (pinfunction "D6_D6") (pintype "bidirectional"))
    )
    (net (code "62") (name "unconnected-(A1-PadD7)") (class "Default")
      (node (ref "A1") (pin "D7") (pinfunction "D7_D7") (pintype "bidirectional"))
    )
    (net (code "63") (name "unconnected-(A1-PadD8)") (class "Default")
      (node (ref "A1") (pin "D8") (pinfunction "D8_D8") (pintype "bidirectional"))
    )
    (net (code "64") (name "unconnected-(A1-PadD9)") (class "Default")
      (node (ref "A1") (pin "D9") (pinfunction "D9_D9") (pintype "bidirectional"))
    )
  )
)
